# ioboard.net
KiCad netlist of a schematic drawn in EAGLE
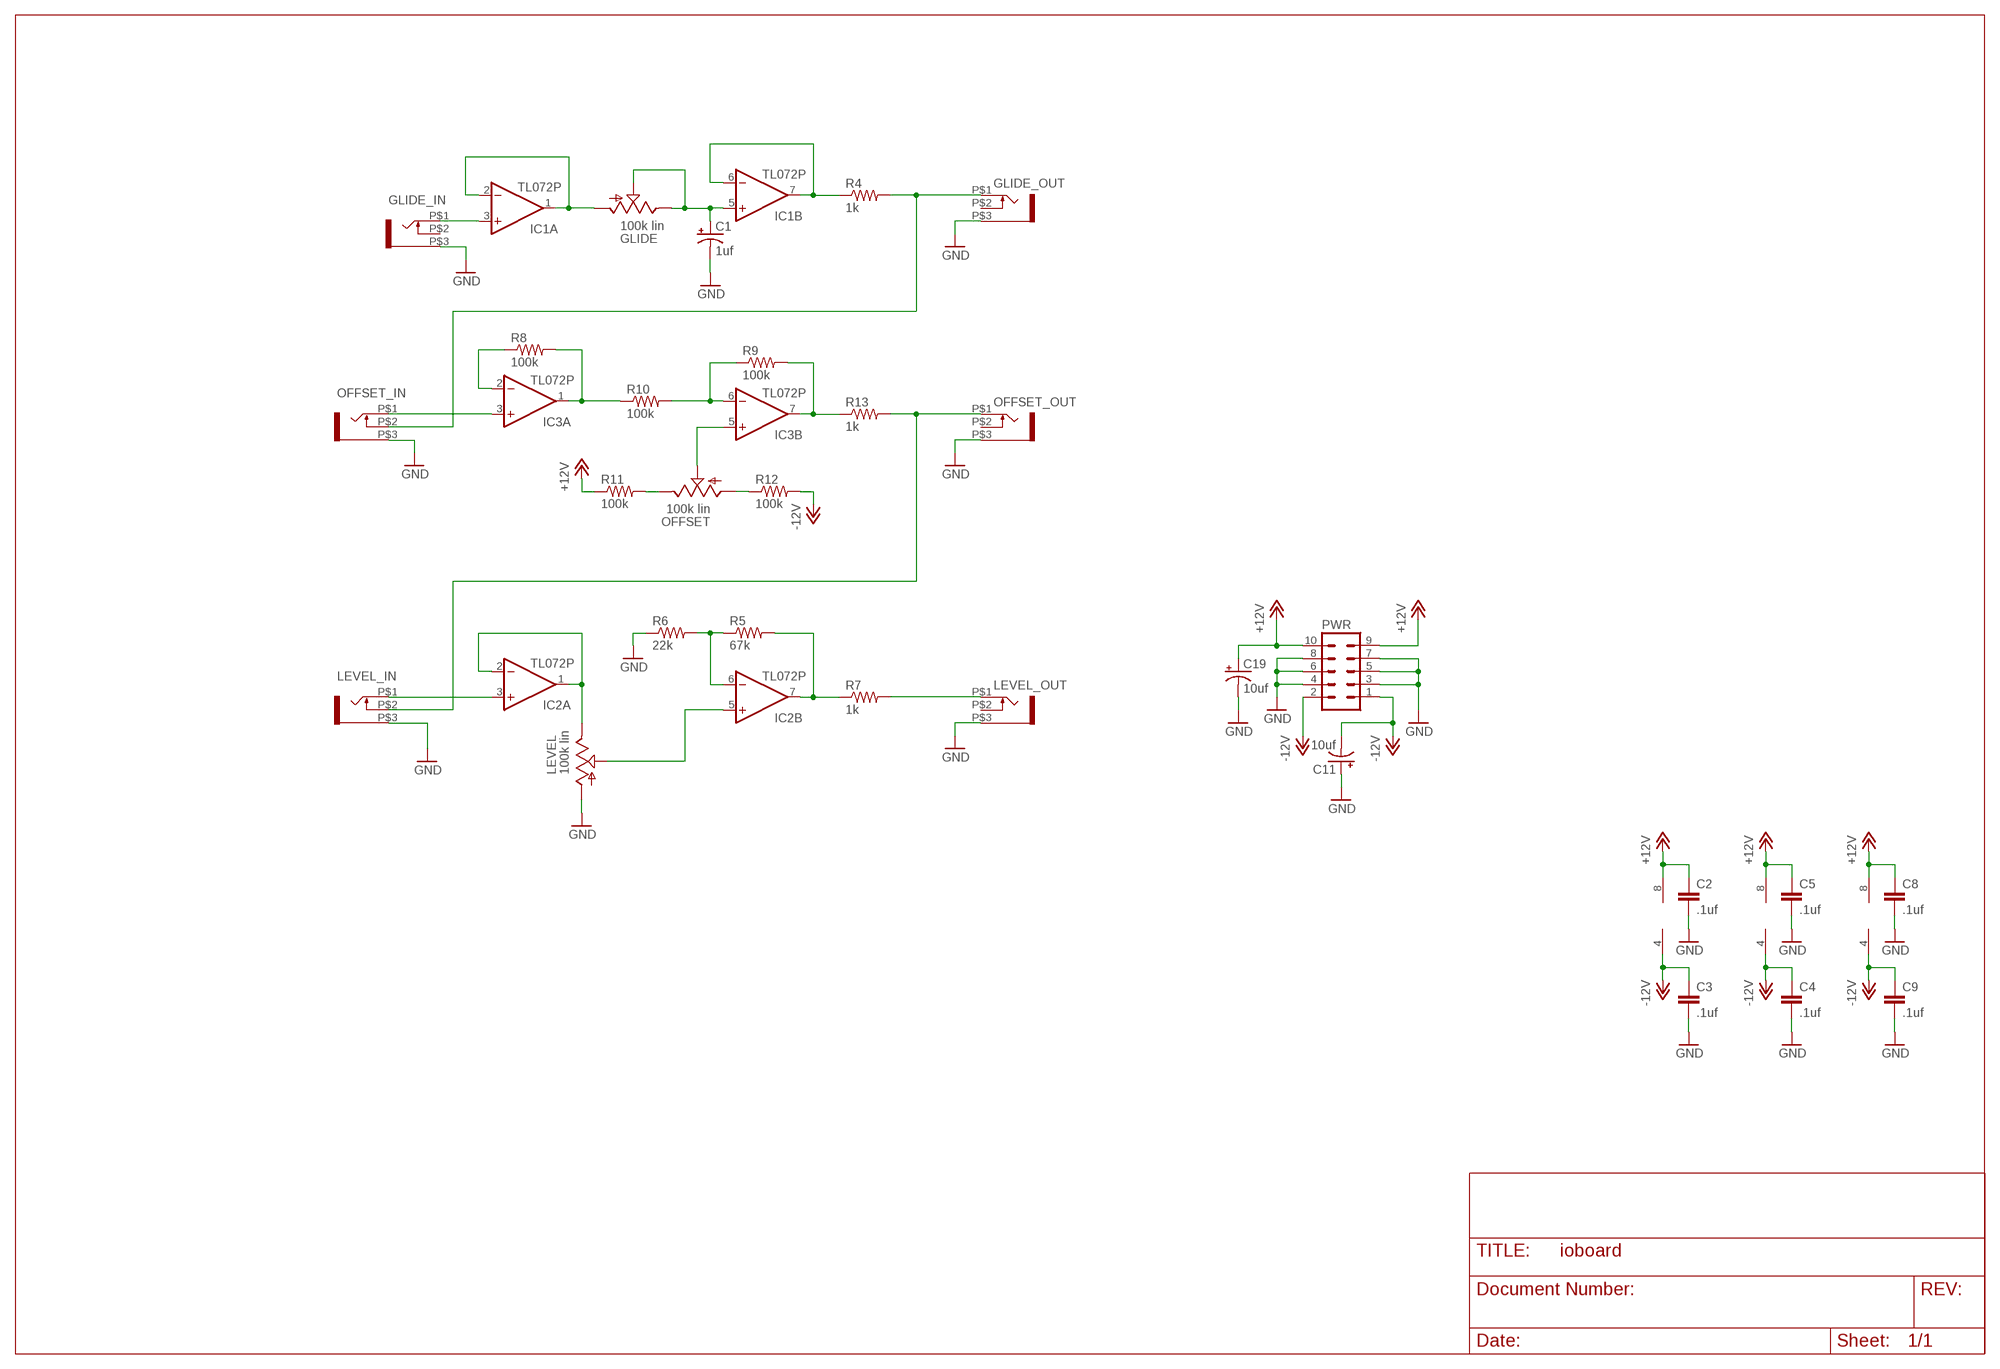
[diagram p0: schematic, sheet 1]

(export (version "E")
  (design (tool "Eeschema 10.0.6"))
  (components
    (comp (ref "C1")
      (value "1uf")
      (footprint "eagle-import:E2,5-6")
      (libsource (lib "eagle-import") (part "CPOL-USE2.5-6"))
    )
    (comp (ref "C2")
      (value ".1uf")
      (footprint "eagle-import:C050-024X044")
      (libsource (lib "eagle-import") (part "C-EU050-024X044"))
    )
    (comp (ref "C3")
      (value ".1uf")
      (footprint "eagle-import:C050-024X044")
      (libsource (lib "eagle-import") (part "C-EU050-024X044"))
    )
    (comp (ref "C4")
      (value ".1uf")
      (footprint "eagle-import:C050-024X044")
      (libsource (lib "eagle-import") (part "C-EU050-024X044"))
    )
    (comp (ref "C5")
      (value ".1uf")
      (footprint "eagle-import:C050-024X044")
      (libsource (lib "eagle-import") (part "C-EU050-024X044"))
    )
    (comp (ref "C8")
      (value ".1uf")
      (footprint "eagle-import:C050-024X044")
      (libsource (lib "eagle-import") (part "C-EU050-024X044"))
    )
    (comp (ref "C9")
      (value ".1uf")
      (footprint "eagle-import:C050-024X044")
      (libsource (lib "eagle-import") (part "C-EU050-024X044"))
    )
    (comp (ref "C11")
      (value "10uf")
      (footprint "eagle-import:E2,5-5")
      (libsource (lib "eagle-import") (part "CPOL-USE2.5-5"))
    )
    (comp (ref "C19")
      (value "10uf")
      (footprint "eagle-import:E2,5-5")
      (libsource (lib "eagle-import") (part "CPOL-USE2.5-5"))
    )
    (comp (ref "GLIDE")
      (value "100k lin")
      (footprint "eagle-import:EVUF")
      (libsource (lib "eagle-import") (part "ALPHA-9MMA"))
    )
    (comp (ref "GLIDE_IN")
      (value "WQP-PJ301M-12_JACK")
      (footprint "eagle-import:WQP-PJ301M-12_JACK")
      (libsource (lib "eagle-import") (part "WQP-PJ301M-12_JACK"))
    )
    (comp (ref "GLIDE_OUT")
      (value "WQP-PJ301M-12_JACK")
      (footprint "eagle-import:WQP-PJ301M-12_JACK")
      (libsource (lib "eagle-import") (part "WQP-PJ301M-12_JACK"))
    )
    (comp (ref "IC1")
      (value "TL072P")
      (footprint "eagle-import:DIL08")
      (libsource (lib "eagle-import") (part "TL072P"))
    )
    (comp (ref "IC2")
      (value "TL072P")
      (footprint "eagle-import:DIL08")
      (libsource (lib "eagle-import") (part "TL072P"))
    )
    (comp (ref "IC3")
      (value "TL072P")
      (footprint "eagle-import:DIL08")
      (libsource (lib "eagle-import") (part "TL072P"))
    )
    (comp (ref "LEVEL")
      (value "100k lin")
      (footprint "eagle-import:EVUF")
      (libsource (lib "eagle-import") (part "ALPHA-9MMA"))
    )
    (comp (ref "LEVEL_IN")
      (value "WQP-PJ301M-12_JACK")
      (footprint "eagle-import:WQP-PJ301M-12_JACK")
      (libsource (lib "eagle-import") (part "WQP-PJ301M-12_JACK"))
    )
    (comp (ref "LEVEL_OUT")
      (value "WQP-PJ301M-12_JACK")
      (footprint "eagle-import:WQP-PJ301M-12_JACK")
      (libsource (lib "eagle-import") (part "WQP-PJ301M-12_JACK"))
    )
    (comp (ref "OFFSET")
      (value "100k lin")
      (footprint "eagle-import:EVUF")
      (libsource (lib "eagle-import") (part "ALPHA-9MMA"))
    )
    (comp (ref "OFFSET_IN")
      (value "WQP-PJ301M-12_JACK")
      (footprint "eagle-import:WQP-PJ301M-12_JACK")
      (libsource (lib "eagle-import") (part "WQP-PJ301M-12_JACK"))
    )
    (comp (ref "OFFSET_OUT")
      (value "WQP-PJ301M-12_JACK")
      (footprint "eagle-import:WQP-PJ301M-12_JACK")
      (libsource (lib "eagle-import") (part "WQP-PJ301M-12_JACK"))
    )
    (comp (ref "PWR")
      (value "ML10")
      (footprint "eagle-import:ML10")
      (libsource (lib "eagle-import") (part "ML10"))
    )
    (comp (ref "R4")
      (value "1k")
      (footprint "eagle-import:0204_7")
      (libsource (lib "eagle-import") (part "R-US_0204/7"))
    )
    (comp (ref "R5")
      (value "67k")
      (footprint "eagle-import:0204_7")
      (libsource (lib "eagle-import") (part "R-US_0204/7"))
    )
    (comp (ref "R6")
      (value "22k")
      (footprint "eagle-import:0204_7")
      (libsource (lib "eagle-import") (part "R-US_0204/7"))
    )
    (comp (ref "R7")
      (value "1k")
      (footprint "eagle-import:0204_7")
      (libsource (lib "eagle-import") (part "R-US_0204/7"))
    )
    (comp (ref "R8")
      (value "100k")
      (footprint "eagle-import:0204_7")
      (libsource (lib "eagle-import") (part "R-US_0204/7"))
    )
    (comp (ref "R9")
      (value "100k")
      (footprint "eagle-import:0204_7")
      (libsource (lib "eagle-import") (part "R-US_0204/7"))
    )
    (comp (ref "R10")
      (value "100k")
      (footprint "eagle-import:0204_7")
      (libsource (lib "eagle-import") (part "R-US_0204/7"))
    )
    (comp (ref "R11")
      (value "100k")
      (footprint "eagle-import:0204_7")
      (libsource (lib "eagle-import") (part "R-US_0204/7"))
    )
    (comp (ref "R12")
      (value "100k")
      (footprint "eagle-import:0204_7")
      (libsource (lib "eagle-import") (part "R-US_0204/7"))
    )
    (comp (ref "R13")
      (value "1k")
      (footprint "eagle-import:0204_7")
      (libsource (lib "eagle-import") (part "R-US_0204/7"))
    )
  )
  (nets
    (net (code "1") (name "+12V") (class "Default")
      (node (ref "C19") (pin "+") (pinfunction "+_+") (pintype "passive"))
      (node (ref "C2") (pin "1") (pinfunction "1_1") (pintype "passive"))
      (node (ref "C5") (pin "1") (pinfunction "1_1") (pintype "passive"))
      (node (ref "C8") (pin "1") (pinfunction "1_1") (pintype "passive"))
      (node (ref "IC1") (pin "8") (pinfunction "V+_8") (pintype "power_in"))
      (node (ref "IC2") (pin "8") (pinfunction "V+_8") (pintype "power_in"))
      (node (ref "IC3") (pin "8") (pinfunction "V+_8") (pintype "power_in"))
      (node (ref "PWR") (pin "10") (pinfunction "10_10") (pintype "passive"))
      (node (ref "PWR") (pin "9") (pinfunction "9_9") (pintype "passive"))
      (node (ref "R11") (pin "1") (pinfunction "1_1") (pintype "passive"))
    )
    (net (code "2") (name "-12V") (class "Default")
      (node (ref "C11") (pin "-") (pinfunction "-_-") (pintype "passive"))
      (node (ref "C3") (pin "1") (pinfunction "1_1") (pintype "passive"))
      (node (ref "C4") (pin "1") (pinfunction "1_1") (pintype "passive"))
      (node (ref "C9") (pin "1") (pinfunction "1_1") (pintype "passive"))
      (node (ref "IC1") (pin "4") (pinfunction "V-_4") (pintype "power_in"))
      (node (ref "IC2") (pin "4") (pinfunction "V-_4") (pintype "power_in"))
      (node (ref "IC3") (pin "4") (pinfunction "V-_4") (pintype "power_in"))
      (node (ref "PWR") (pin "1") (pinfunction "1_1") (pintype "passive"))
      (node (ref "PWR") (pin "2") (pinfunction "2_2") (pintype "passive"))
      (node (ref "R12") (pin "2") (pinfunction "2_2") (pintype "passive"))
    )
    (net (code "3") (name "GND") (class "Default")
      (node (ref "C1") (pin "-") (pinfunction "-_-") (pintype "passive"))
      (node (ref "C11") (pin "+") (pinfunction "+_+") (pintype "passive"))
      (node (ref "C19") (pin "-") (pinfunction "-_-") (pintype "passive"))
      (node (ref "C2") (pin "2") (pinfunction "2_2") (pintype "passive"))
      (node (ref "C3") (pin "2") (pinfunction "2_2") (pintype "passive"))
      (node (ref "C4") (pin "2") (pinfunction "2_2") (pintype "passive"))
      (node (ref "C5") (pin "2") (pinfunction "2_2") (pintype "passive"))
      (node (ref "C8") (pin "2") (pinfunction "2_2") (pintype "passive"))
      (node (ref "C9") (pin "2") (pinfunction "2_2") (pintype "passive"))
      (node (ref "GLIDE_IN") (pin "P$3") (pinfunction "1_P$3") (pintype "passive"))
      (node (ref "GLIDE_OUT") (pin "P$3") (pinfunction "1_P$3") (pintype "passive"))
      (node (ref "LEVEL") (pin "1") (pinfunction "A_1") (pintype "passive"))
      (node (ref "LEVEL_IN") (pin "P$3") (pinfunction "1_P$3") (pintype "passive"))
      (node (ref "LEVEL_OUT") (pin "P$3") (pinfunction "1_P$3") (pintype "passive"))
      (node (ref "OFFSET_IN") (pin "P$3") (pinfunction "1_P$3") (pintype "passive"))
      (node (ref "OFFSET_OUT") (pin "P$3") (pinfunction "1_P$3") (pintype "passive"))
      (node (ref "PWR") (pin "3") (pinfunction "3_3") (pintype "passive"))
      (node (ref "PWR") (pin "4") (pinfunction "4_4") (pintype "passive"))
      (node (ref "PWR") (pin "5") (pinfunction "5_5") (pintype "passive"))
      (node (ref "PWR") (pin "6") (pinfunction "6_6") (pintype "passive"))
      (node (ref "PWR") (pin "7") (pinfunction "7_7") (pintype "passive"))
      (node (ref "PWR") (pin "8") (pinfunction "8_8") (pintype "passive"))
      (node (ref "R6") (pin "1") (pinfunction "1_1") (pintype "passive"))
    )
    (net (code "4") (name "Net-(GLIDE-A)") (class "Default")
      (node (ref "GLIDE") (pin "1") (pinfunction "A_1") (pintype "passive"))
      (node (ref "IC1") (pin "1") (pinfunction "OUT_1") (pintype "output"))
      (node (ref "IC1") (pin "2") (pinfunction "-IN_2") (pintype "input"))
    )
    (net (code "5") (name "Net-(GLIDE-E)") (class "Default")
      (node (ref "C1") (pin "+") (pinfunction "+_+") (pintype "passive"))
      (node (ref "GLIDE") (pin "2") (pinfunction "S_2") (pintype "passive"))
      (node (ref "GLIDE") (pin "3") (pinfunction "E_3") (pintype "passive"))
      (node (ref "IC1") (pin "5") (pinfunction "+IN_5") (pintype "input"))
    )
    (net (code "6") (name "Net-(GLIDE_IN-2)") (class "Default")
      (node (ref "GLIDE_IN") (pin "P$1") (pinfunction "2_P$1") (pintype "passive"))
      (node (ref "IC1") (pin "3") (pinfunction "+IN_3") (pintype "input"))
    )
    (net (code "7") (name "Net-(GLIDE_OUT-2)") (class "Default")
      (node (ref "GLIDE_OUT") (pin "P$1") (pinfunction "2_P$1") (pintype "passive"))
      (node (ref "OFFSET_IN") (pin "P$2") (pinfunction "3_P$2") (pintype "passive"))
      (node (ref "R4") (pin "2") (pinfunction "2_2") (pintype "passive"))
    )
    (net (code "8") (name "Net-(IC1B--IN)") (class "Default")
      (node (ref "IC1") (pin "6") (pinfunction "-IN_6") (pintype "input"))
      (node (ref "IC1") (pin "7") (pinfunction "OUT_7") (pintype "output"))
      (node (ref "R4") (pin "1") (pinfunction "1_1") (pintype "passive"))
    )
    (net (code "9") (name "Net-(IC2A-+IN)") (class "Default")
      (node (ref "IC2") (pin "3") (pinfunction "+IN_3") (pintype "input"))
      (node (ref "LEVEL_IN") (pin "P$1") (pinfunction "2_P$1") (pintype "passive"))
    )
    (net (code "10") (name "Net-(IC2A--IN)") (class "Default")
      (node (ref "IC2") (pin "1") (pinfunction "OUT_1") (pintype "output"))
      (node (ref "IC2") (pin "2") (pinfunction "-IN_2") (pintype "input"))
      (node (ref "LEVEL") (pin "3") (pinfunction "E_3") (pintype "passive"))
    )
    (net (code "11") (name "Net-(IC2B-+IN)") (class "Default")
      (node (ref "IC2") (pin "5") (pinfunction "+IN_5") (pintype "input"))
      (node (ref "LEVEL") (pin "2") (pinfunction "S_2") (pintype "passive"))
    )
    (net (code "12") (name "Net-(IC2B--IN)") (class "Default")
      (node (ref "IC2") (pin "6") (pinfunction "-IN_6") (pintype "input"))
      (node (ref "R5") (pin "1") (pinfunction "1_1") (pintype "passive"))
      (node (ref "R6") (pin "2") (pinfunction "2_2") (pintype "passive"))
    )
    (net (code "13") (name "Net-(IC2B-OUT)") (class "Default")
      (node (ref "IC2") (pin "7") (pinfunction "OUT_7") (pintype "output"))
      (node (ref "R5") (pin "2") (pinfunction "2_2") (pintype "passive"))
      (node (ref "R7") (pin "1") (pinfunction "1_1") (pintype "passive"))
    )
    (net (code "14") (name "Net-(IC3A-+IN)") (class "Default")
      (node (ref "IC3") (pin "3") (pinfunction "+IN_3") (pintype "input"))
      (node (ref "OFFSET_IN") (pin "P$1") (pinfunction "2_P$1") (pintype "passive"))
    )
    (net (code "15") (name "Net-(IC3A--IN)") (class "Default")
      (node (ref "IC3") (pin "2") (pinfunction "-IN_2") (pintype "input"))
      (node (ref "R8") (pin "1") (pinfunction "1_1") (pintype "passive"))
    )
    (net (code "16") (name "Net-(IC3A-OUT)") (class "Default")
      (node (ref "IC3") (pin "1") (pinfunction "OUT_1") (pintype "output"))
      (node (ref "R10") (pin "1") (pinfunction "1_1") (pintype "passive"))
      (node (ref "R8") (pin "2") (pinfunction "2_2") (pintype "passive"))
    )
    (net (code "17") (name "Net-(IC3B-+IN)") (class "Default")
      (node (ref "IC3") (pin "5") (pinfunction "+IN_5") (pintype "input"))
      (node (ref "OFFSET") (pin "2") (pinfunction "S_2") (pintype "passive"))
    )
    (net (code "18") (name "Net-(IC3B--IN)") (class "Default")
      (node (ref "IC3") (pin "6") (pinfunction "-IN_6") (pintype "input"))
      (node (ref "R10") (pin "2") (pinfunction "2_2") (pintype "passive"))
      (node (ref "R9") (pin "1") (pinfunction "1_1") (pintype "passive"))
    )
    (net (code "19") (name "Net-(IC3B-OUT)") (class "Default")
      (node (ref "IC3") (pin "7") (pinfunction "OUT_7") (pintype "output"))
      (node (ref "R13") (pin "1") (pinfunction "1_1") (pintype "passive"))
      (node (ref "R9") (pin "2") (pinfunction "2_2") (pintype "passive"))
    )
    (net (code "20") (name "Net-(LEVEL_IN-3)") (class "Default")
      (node (ref "LEVEL_IN") (pin "P$2") (pinfunction "3_P$2") (pintype "passive"))
      (node (ref "OFFSET_OUT") (pin "P$1") (pinfunction "2_P$1") (pintype "passive"))
      (node (ref "R13") (pin "2") (pinfunction "2_2") (pintype "passive"))
    )
    (net (code "21") (name "Net-(LEVEL_OUT-2)") (class "Default")
      (node (ref "LEVEL_OUT") (pin "P$1") (pinfunction "2_P$1") (pintype "passive"))
      (node (ref "R7") (pin "2") (pinfunction "2_2") (pintype "passive"))
    )
    (net (code "22") (name "Net-(OFFSET-A)") (class "Default")
      (node (ref "OFFSET") (pin "1") (pinfunction "A_1") (pintype "passive"))
      (node (ref "R12") (pin "1") (pinfunction "1_1") (pintype "passive"))
    )
    (net (code "23") (name "Net-(OFFSET-E)") (class "Default")
      (node (ref "OFFSET") (pin "3") (pinfunction "E_3") (pintype "passive"))
      (node (ref "R11") (pin "2") (pinfunction "2_2") (pintype "passive"))
    )
    (net (code "24") (name "unconnected-(GLIDE_IN-3-PadP$2)") (class "Default")
      (node (ref "GLIDE_IN") (pin "P$2") (pinfunction "3_P$2") (pintype "passive"))
    )
    (net (code "25") (name "unconnected-(GLIDE_OUT-3-PadP$2)") (class "Default")
      (node (ref "GLIDE_OUT") (pin "P$2") (pinfunction "3_P$2") (pintype "passive"))
    )
    (net (code "26") (name "unconnected-(LEVEL_OUT-3-PadP$2)") (class "Default")
      (node (ref "LEVEL_OUT") (pin "P$2") (pinfunction "3_P$2") (pintype "passive"))
    )
    (net (code "27") (name "unconnected-(OFFSET_OUT-3-PadP$2)") (class "Default")
      (node (ref "OFFSET_OUT") (pin "P$2") (pinfunction "3_P$2") (pintype "passive"))
    )
  )
)
